# DDC.net
KiCad netlist of a schematic drawn in Altium Designer
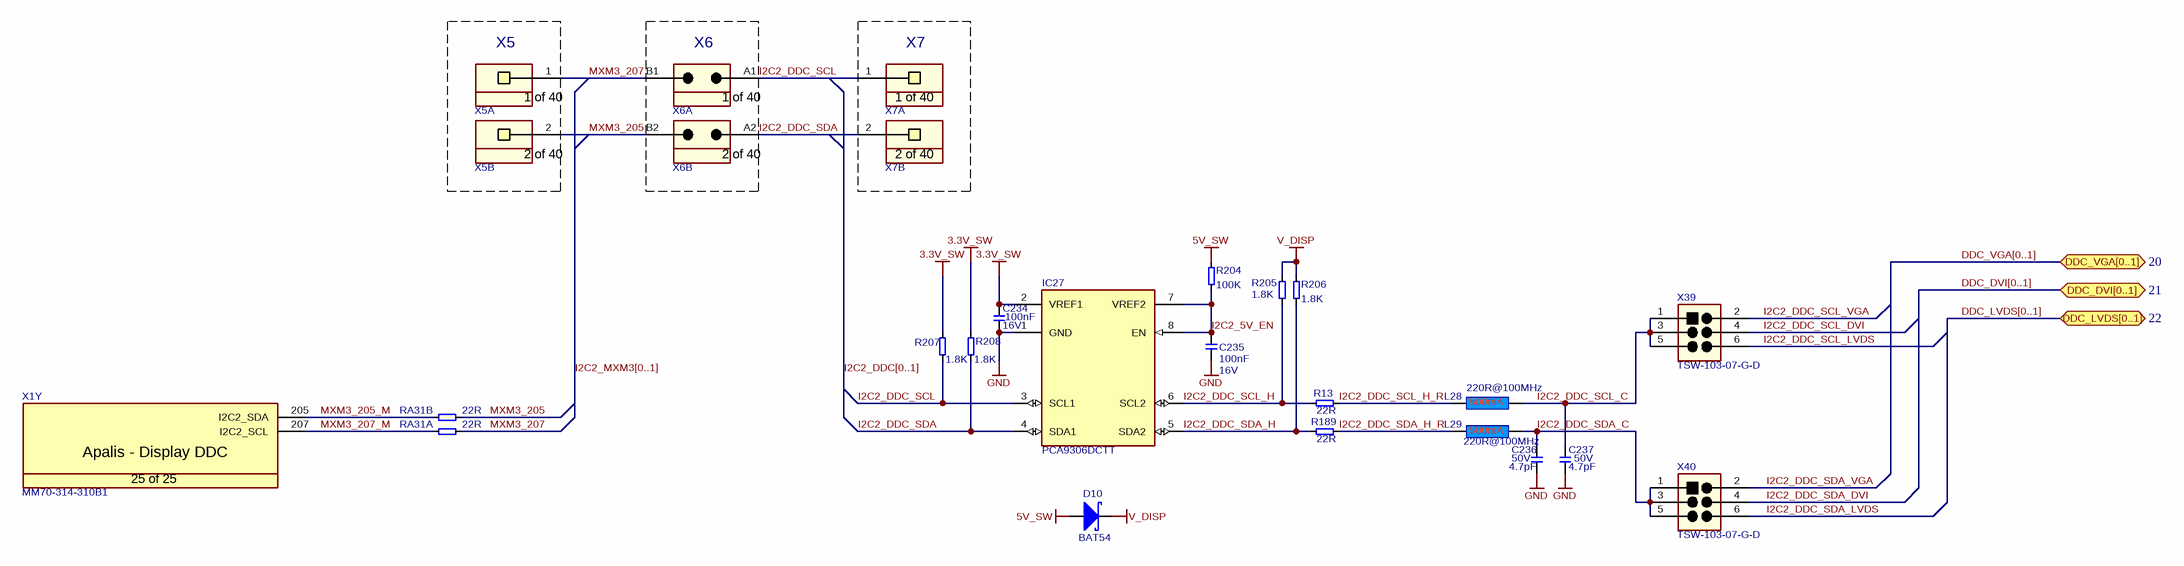
[diagram p0: DDC.SchDoc]

(export (version "E")
  (design (tool "Eeschema 10.0.6"))
  (components
    (comp (ref "C234")
      (value "100nF")
      (footprint "T_CAPC0603X33N")
      (description "Capacitor Ceramic X7R 100nF 16V 10% 0603")
      (fields (field (name "TOLERANCE") "10%") (field (name "RATING") "16V"))
      (libsource (lib "Apalis Evaluation Board") (part "C-X7R-100nF-16V-10%-0603"))
    )
    (comp (ref "C235")
      (value "100nF")
      (footprint "T_CAPC0603X33N")
      (description "Capacitor Ceramic X7R 100nF 16V 10% 0603")
      (fields (field (name "TOLERANCE") "10%") (field (name "RATING") "16V"))
      (libsource (lib "Apalis Evaluation Board") (part "C-X7R-100nF-16V-10%-0603"))
    )
    (comp (ref "C236")
      (value "4.7pF")
      (footprint "T_CAPC0603X33N")
      (description "Capacitor Ceramic NP0  4.7pF 25V 10% 0603")
      (fields (field (name "TOLERANCE") "10%") (field (name "RATING") "50V"))
      (libsource (lib "Apalis Evaluation Board") (part "C-NP0-4.7pF-25V-10%-0603"))
    )
    (comp (ref "C237")
      (value "4.7pF")
      (footprint "T_CAPC0603X33N")
      (description "Capacitor Ceramic NP0  4.7pF 25V 10% 0603")
      (fields (field (name "TOLERANCE") "10%") (field (name "RATING") "50V"))
      (libsource (lib "Apalis Evaluation Board") (part "C-NP0-4.7pF-25V-10%-0603"))
    )
    (comp (ref "D10")
      (value "BAT54")
      (footprint "SOT95P230X110-3N")
      (description "BAT54 Schottky Diode")
      (fields (field (name "MANUFACTURER PART NO.") "BAT54"))
      (libsource (lib "Apalis Evaluation Board") (part "D-Philips-BAT54-Schottky"))
    )
    (comp (ref "IC27")
      (value "PCA9306DCTT")
      (footprint "T_TI_PCA9306DCTT")
      (description "Dual Bidirectional I2C and SMBus Voltage-Level Translator")
      (fields (field (name "MANUFACTURER PART NO.") "PCA9306DCTT"))
      (libsource (lib "Apalis Evaluation Board") (part "IC-TI-PCA9306DCTT"))
    )
    (comp (ref "L28")
      (value "220R@100MHz")
      (footprint "INDC1608X95N")
      (description "220R@100MHz 500mA EMI FILTER")
      (fields (field (name "TOLERANCE") "25%"))
      (libsource (lib "Apalis Evaluation Board") (part "L-220R@100MHz-500mA-25%-0603"))
    )
    (comp (ref "L29")
      (value "220R@100MHz")
      (footprint "INDC1608X95N")
      (description "220R@100MHz 500mA EMI FILTER")
      (fields (field (name "TOLERANCE") "25%"))
      (libsource (lib "Apalis Evaluation Board") (part "L-220R@100MHz-500mA-25%-0603"))
    )
    (comp (ref "R13")
      (value "22R")
      (footprint "T_RESC0603X30N")
      (description "Resistor 22 ohm 63mW 5% 0603")
      (fields (field (name "TOLERANCE") "5%"))
      (libsource (lib "Apalis Evaluation Board") (part "R-22R-63mW-5%-0603"))
    )
    (comp (ref "R189")
      (value "22R")
      (footprint "T_RESC0603X30N")
      (description "Resistor 22 ohm 63mW 5% 0603")
      (fields (field (name "TOLERANCE") "5%"))
      (libsource (lib "Apalis Evaluation Board") (part "R-22R-63mW-5%-0603"))
    )
    (comp (ref "R204")
      (value "100K")
      (footprint "T_RESC0603X30N")
      (description "Resistor 100 Kohm 63mW 5% 0603")
      (fields (field (name "TOLERANCE") "5%"))
      (libsource (lib "Apalis Evaluation Board") (part "R-100KR-63mW-5%-0603"))
    )
    (comp (ref "R205")
      (value "1.8K")
      (footprint "T_RESC0603X30N")
      (description "Resistor 1.8 Kohm 63mW 5% 0603")
      (fields (field (name "TOLERANCE") "5%"))
      (libsource (lib "Apalis Evaluation Board") (part "R-1.8KR-63mW-5%-0603"))
    )
    (comp (ref "R206")
      (value "1.8K")
      (footprint "T_RESC0603X30N")
      (description "Resistor 1.8 Kohm 63mW 5% 0603")
      (fields (field (name "TOLERANCE") "5%"))
      (libsource (lib "Apalis Evaluation Board") (part "R-1.8KR-63mW-5%-0603"))
    )
    (comp (ref "R207")
      (value "1.8K")
      (footprint "T_RESC0603X30N")
      (description "Resistor 1.8 Kohm 63mW 5% 0603")
      (fields (field (name "TOLERANCE") "5%"))
      (libsource (lib "Apalis Evaluation Board") (part "R-1.8KR-63mW-5%-0603"))
    )
    (comp (ref "R208")
      (value "1.8K")
      (footprint "T_RESC0603X30N")
      (description "Resistor 1.8 Kohm 63mW 5% 0603")
      (fields (field (name "TOLERANCE") "5%"))
      (libsource (lib "Apalis Evaluation Board") (part "R-1.8KR-63mW-5%-0603"))
    )
    (comp (ref "RA31")
      (value "22R")
      (footprint "T_Resistor_Array_X4")
      (description "Resistor Array 22 R 63mW 5% 1206")
      (fields (field (name "TOLERANCE") "5%"))
      (libsource (lib "Apalis Evaluation Board") (part "RA-22R-63mW-5%-1206-div"))
    )
    (comp (ref "X1")
      (value "CON-JAE-MM70-314-310B1-314-0.5mm")
      (footprint "T_JAE_MM70-314-310B1")
      (description "MXM3 Connector")
      (fields (field (name "MANUFACTURER PART NO.") "MM70-314-310B1"))
      (libsource (lib "Apalis Evaluation Board") (part "CON-JAE-MM70-314-310B1-314-0.5mm"))
    )
    (comp (ref "X5")
      (value "SSW-110-01-G-S")
      (footprint "T_Samtec_SSW-110-01-G-S")
      (description "Receptacle Female Socket 1x40 pin 2.54mm pitch")
      (libsource (lib "Apalis Evaluation Board") (part "CON-Samtec-SSW-110-01-G-S"))
    )
    (comp (ref "X6")
      (value "TSW-110-07-G-D")
      (footprint "T_Samtec_TSW-110-07-G-D")
      (description "Header 2x40 pin 2.54mm pitch")
      (libsource (lib "Apalis Evaluation Board") (part "CON-Samtec-TSW-110-07-G-D"))
    )
    (comp (ref "X7")
      (value "SSW-110-01-G-S")
      (footprint "T_Samtec_SSW-110-01-G-S")
      (description "Receptacle Female Socket 1x40 pin 2.54mm pitch")
      (libsource (lib "") (part "CON-Samtec-SSW-110-01-G-S_1"))
    )
    (comp (ref "X39")
      (value "TSW-103-07-G-D")
      (footprint "T_Samtec_TSW-103-07-G-D")
      (description "Header Male, 2x3 Pins, 2.54mm pitch")
      (fields (field (name "MANUFACTURER PART NO.") "TSW-103-07-G-D"))
      (libsource (lib "Apalis Evaluation Board") (part "CON-Samtec-TSW-103-07-G-D-SIM"))
    )
    (comp (ref "X40")
      (value "TSW-103-07-G-D")
      (footprint "T_Samtec_TSW-103-07-G-D")
      (description "Header Male, 2x3 Pins, 2.54mm pitch")
      (fields (field (name "MANUFACTURER PART NO.") "TSW-103-07-G-D"))
      (libsource (lib "Apalis Evaluation Board") (part "CON-Samtec-TSW-103-07-G-D-SIM"))
    )
  )
  (nets
    (net (code "14") (name "/I2C2_5V_EN") (class "Default")
      (node (ref "C235") (pin "2") (pinfunction "2_2") (pintype "passive"))
      (node (ref "IC27") (pin "7") (pinfunction "VREF2_7") (pintype "power_in"))
      (node (ref "IC27") (pin "8") (pinfunction "EN_8") (pintype "input"))
      (node (ref "R204") (pin "1") (pinfunction "1_1") (pintype "passive"))
    )
    (net (code "16") (name "/I2C2_DDC_SCL") (class "Default")
      (node (ref "IC27") (pin "3") (pinfunction "SCL1_3") (pintype "bidirectional"))
      (node (ref "R207") (pin "1") (pinfunction "1_1") (pintype "passive"))
      (node (ref "X6") (pin "A1") (pinfunction "A1_A1") (pintype "passive"))
      (node (ref "X7") (pin "1") (pinfunction "1_1") (pintype "passive"))
    )
    (net (code "17") (name "/I2C2_DDC_SCL_C") (class "Default")
      (node (ref "C237") (pin "1") (pinfunction "1_1") (pintype "passive"))
      (node (ref "L28") (pin "2") (pinfunction "2_2") (pintype "passive"))
      (node (ref "X39") (pin "1") (pinfunction "1_1") (pintype "passive"))
      (node (ref "X39") (pin "3") (pinfunction "3_3") (pintype "passive"))
      (node (ref "X39") (pin "5") (pinfunction "5_5") (pintype "passive"))
    )
    (net (code "18") (name "/I2C2_DDC_SCL_DVI") (class "Default")
      (node (ref "X39") (pin "4") (pinfunction "4_4") (pintype "passive"))
    )
    (net (code "19") (name "/I2C2_DDC_SCL_H") (class "Default")
      (node (ref "IC27") (pin "6") (pinfunction "SCL2_6") (pintype "bidirectional"))
      (node (ref "R13") (pin "1") (pinfunction "1_1") (pintype "passive"))
      (node (ref "R205") (pin "2") (pinfunction "2_2") (pintype "passive"))
    )
    (net (code "20") (name "/I2C2_DDC_SCL_H_R") (class "Default")
      (node (ref "L28") (pin "1") (pinfunction "1_1") (pintype "passive"))
      (node (ref "R13") (pin "2") (pinfunction "2_2") (pintype "passive"))
    )
    (net (code "21") (name "/I2C2_DDC_SCL_LVDS") (class "Default")
      (node (ref "X39") (pin "6") (pinfunction "6_6") (pintype "passive"))
    )
    (net (code "22") (name "/I2C2_DDC_SCL_VGA") (class "Default")
      (node (ref "X39") (pin "2") (pinfunction "2_2") (pintype "passive"))
    )
    (net (code "23") (name "/I2C2_DDC_SDA") (class "Default")
      (node (ref "IC27") (pin "4") (pinfunction "SDA1_4") (pintype "bidirectional"))
      (node (ref "R208") (pin "1") (pinfunction "1_1") (pintype "passive"))
      (node (ref "X6") (pin "A2") (pinfunction "A2_A2") (pintype "passive"))
      (node (ref "X7") (pin "2") (pinfunction "2_2") (pintype "passive"))
    )
    (net (code "24") (name "/I2C2_DDC_SDA_C") (class "Default")
      (node (ref "C236") (pin "1") (pinfunction "1_1") (pintype "passive"))
      (node (ref "L29") (pin "2") (pinfunction "2_2") (pintype "passive"))
      (node (ref "X40") (pin "1") (pinfunction "1_1") (pintype "passive"))
      (node (ref "X40") (pin "3") (pinfunction "3_3") (pintype "passive"))
      (node (ref "X40") (pin "5") (pinfunction "5_5") (pintype "passive"))
    )
    (net (code "25") (name "/I2C2_DDC_SDA_DVI") (class "Default")
      (node (ref "X40") (pin "4") (pinfunction "4_4") (pintype "passive"))
    )
    (net (code "26") (name "/I2C2_DDC_SDA_H") (class "Default")
      (node (ref "IC27") (pin "5") (pinfunction "SDA2_5") (pintype "bidirectional"))
      (node (ref "R189") (pin "1") (pinfunction "1_1") (pintype "passive"))
      (node (ref "R206") (pin "2") (pinfunction "2_2") (pintype "passive"))
    )
    (net (code "27") (name "/I2C2_DDC_SDA_H_R") (class "Default")
      (node (ref "L29") (pin "1") (pinfunction "1_1") (pintype "passive"))
      (node (ref "R189") (pin "2") (pinfunction "2_2") (pintype "passive"))
    )
    (net (code "28") (name "/I2C2_DDC_SDA_LVDS") (class "Default")
      (node (ref "X40") (pin "6") (pinfunction "6_6") (pintype "passive"))
    )
    (net (code "29") (name "/I2C2_DDC_SDA_VGA") (class "Default")
      (node (ref "X40") (pin "2") (pinfunction "2_2") (pintype "passive"))
    )
    (net (code "31") (name "/MXM3_205") (class "Default")
      (node (ref "RA31") (pin "6") (pinfunction "6_6") (pintype "passive"))
      (node (ref "X5") (pin "2") (pinfunction "2_2") (pintype "passive"))
      (node (ref "X6") (pin "B2") (pinfunction "B2_B2") (pintype "passive"))
    )
    (net (code "32") (name "/MXM3_205_M") (class "Default")
      (node (ref "RA31") (pin "2") (pinfunction "2_2") (pintype "passive"))
      (node (ref "X1") (pin "205") (pinfunction "I2C2_SDA_205") (pintype "passive"))
    )
    (net (code "33") (name "/MXM3_207") (class "Default")
      (node (ref "RA31") (pin "5") (pinfunction "5_5") (pintype "passive"))
      (node (ref "X5") (pin "1") (pinfunction "1_1") (pintype "passive"))
      (node (ref "X6") (pin "B1") (pinfunction "B1_B1") (pintype "passive"))
    )
    (net (code "34") (name "/MXM3_207_M") (class "Default")
      (node (ref "RA31") (pin "1") (pinfunction "1_1") (pintype "passive"))
      (node (ref "X1") (pin "207") (pinfunction "I2C2_SCL_207") (pintype "passive"))
    )
    (net (code "35") (name "3.3V_SW") (class "Default")
      (node (ref "C234") (pin "2") (pinfunction "2_2") (pintype "passive"))
      (node (ref "IC27") (pin "2") (pinfunction "VREF1_2") (pintype "power_in"))
      (node (ref "R207") (pin "2") (pinfunction "2_2") (pintype "passive"))
      (node (ref "R208") (pin "2") (pinfunction "2_2") (pintype "passive"))
    )
    (net (code "36") (name "5V_SW") (class "Default")
      (node (ref "D10") (pin "1") (pinfunction "1_1") (pintype "passive"))
      (node (ref "R204") (pin "2") (pinfunction "2_2") (pintype "passive"))
    )
    (net (code "37") (name "GND") (class "Default")
      (node (ref "C234") (pin "1") (pinfunction "1_1") (pintype "passive"))
      (node (ref "C235") (pin "1") (pinfunction "1_1") (pintype "passive"))
      (node (ref "C236") (pin "2") (pinfunction "2_2") (pintype "passive"))
      (node (ref "C237") (pin "2") (pinfunction "2_2") (pintype "passive"))
      (node (ref "IC27") (pin "1") (pinfunction "GND_1") (pintype "power_in"))
    )
    (net (code "38") (name "V_DISP") (class "Default")
      (node (ref "D10") (pin "3") (pinfunction "3_3") (pintype "passive"))
      (node (ref "R205") (pin "1") (pinfunction "1_1") (pintype "passive"))
      (node (ref "R206") (pin "1") (pinfunction "1_1") (pintype "passive"))
    )
  )
)
